# QuadCopter_Controller.net
KiCad netlist of a schematic drawn in EAGLE
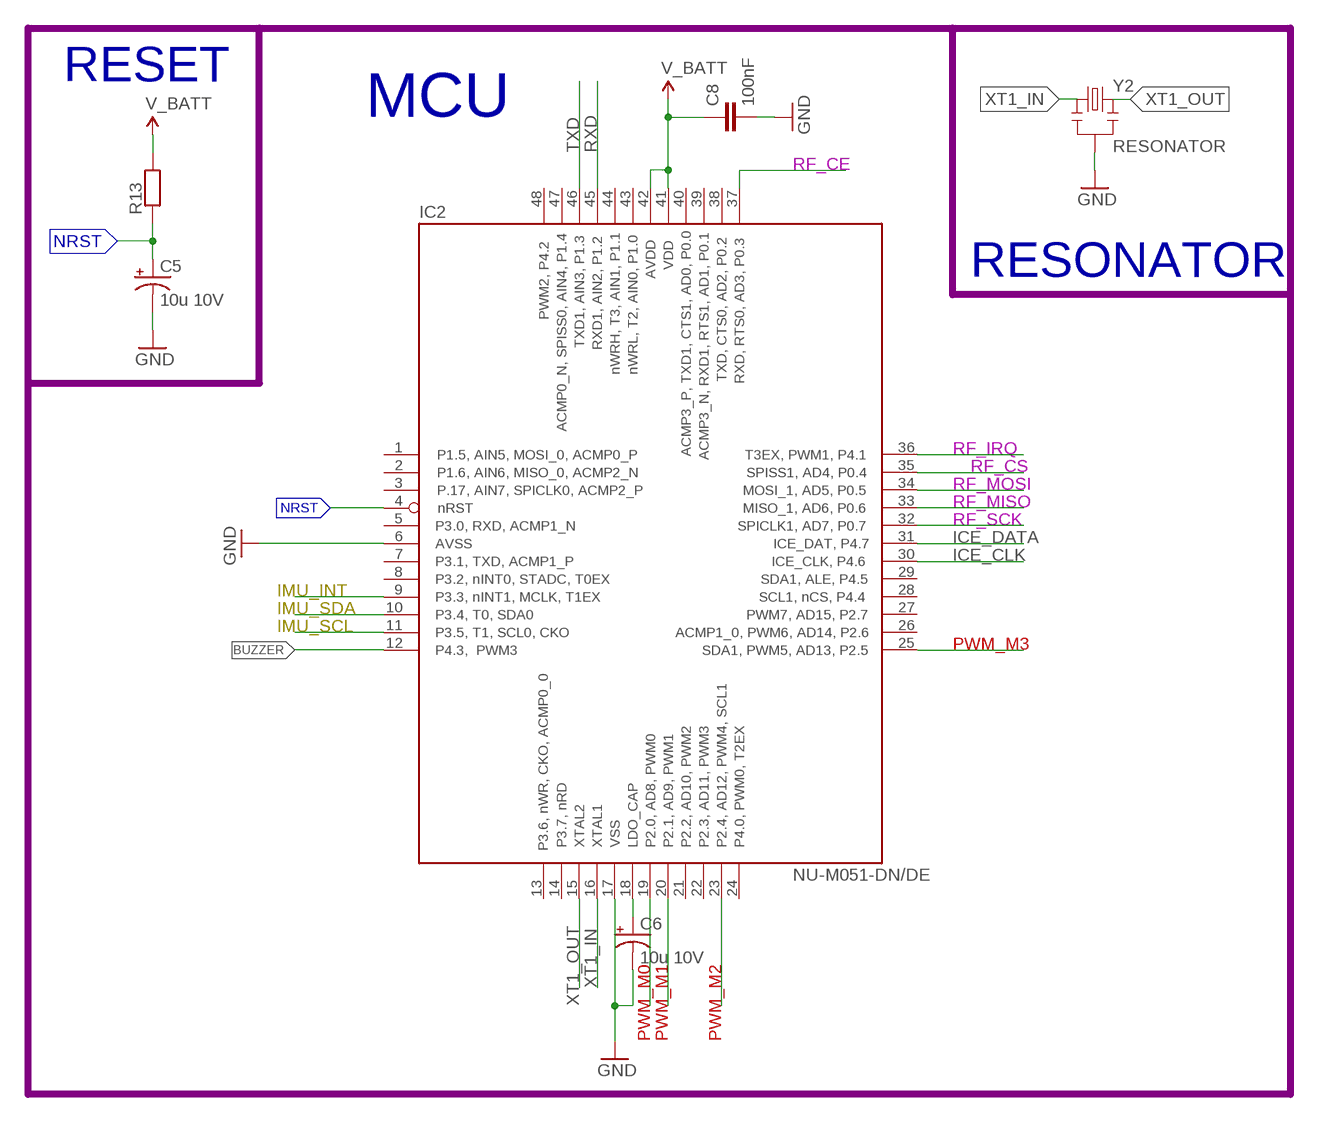
[diagram p0: schematic, sheet 1, part 1 of 2]
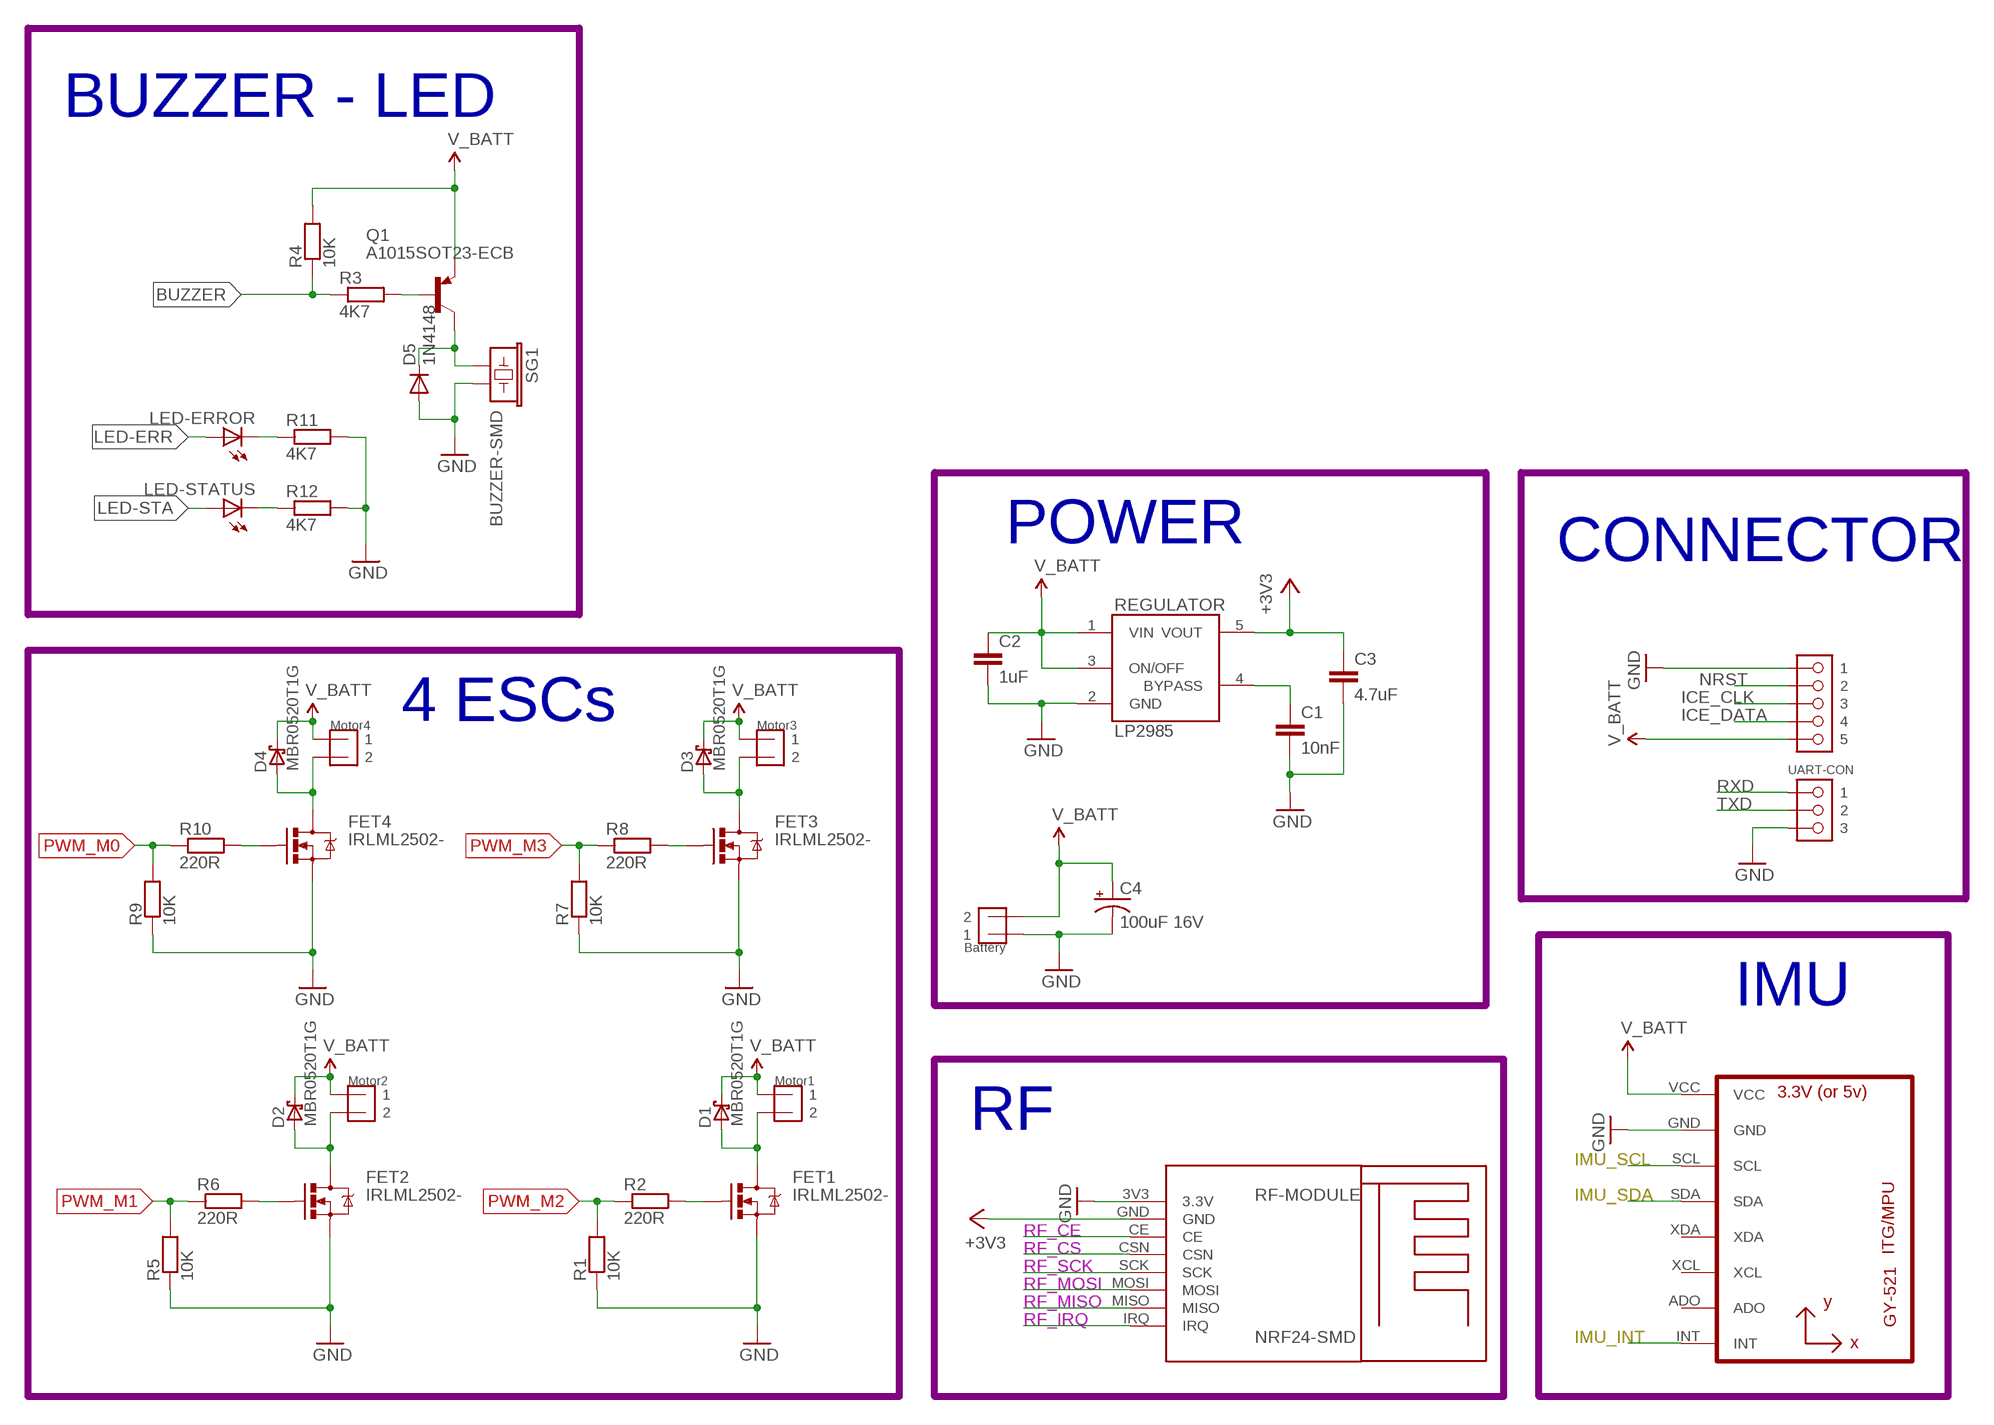
[diagram p1: schematic, sheet 1, part 2 of 2]

(export (version "E")
  (design (tool "Eeschema 10.0.6"))
  (components
    (comp (ref "BATTERY")
      (value "Battery")
      (footprint "eagle-import:WAFER-CON-2P")
      (libsource (lib "eagle-import") (part "WAFER-CON-2P"))
    )
    (comp (ref "C1")
      (value "10nF")
      (footprint "eagle-import:C0603K")
      (libsource (lib "eagle-import") (part "C-SMDC0603K"))
    )
    (comp (ref "C2")
      (value "1uF")
      (footprint "eagle-import:C0603K")
      (libsource (lib "eagle-import") (part "C-SMDC0603K"))
    )
    (comp (ref "C3")
      (value "4.7uF")
      (footprint "eagle-import:C0603K")
      (libsource (lib "eagle-import") (part "C-SMDC0603K"))
    )
    (comp (ref "C4")
      (value "100uF 16V")
      (footprint "eagle-import:PANASONIC_D")
      (libsource (lib "eagle-import") (part "C-ALU-D"))
    )
    (comp (ref "C5")
      (value "10u 10V")
      (footprint "eagle-import:EIA3216")
      (libsource (lib "eagle-import") (part "CAP_POL1206"))
    )
    (comp (ref "C6")
      (value "10u 10V")
      (footprint "eagle-import:EIA3216")
      (libsource (lib "eagle-import") (part "CAP_POL1206"))
    )
    (comp (ref "C8")
      (value "100nF")
      (footprint "eagle-import:C0603K")
      (libsource (lib "eagle-import") (part "C-SMDC0603K"))
    )
    (comp (ref "D1")
      (value "MBR0520T1G")
      (footprint "eagle-import:SOD123")
      (libsource (lib "eagle-import") (part "D-SCKYMBR0520T1G"))
    )
    (comp (ref "D2")
      (value "MBR0520T1G")
      (footprint "eagle-import:SOD123")
      (libsource (lib "eagle-import") (part "D-SCKYMBR0520T1G"))
    )
    (comp (ref "D3")
      (value "MBR0520T1G")
      (footprint "eagle-import:SOD123")
      (libsource (lib "eagle-import") (part "D-SCKYMBR0520T1G"))
    )
    (comp (ref "D4")
      (value "MBR0520T1G")
      (footprint "eagle-import:SOD123")
      (libsource (lib "eagle-import") (part "D-SCKYMBR0520T1G"))
    )
    (comp (ref "D5")
      (value "1N4148")
      (footprint "eagle-import:SOD123")
      (libsource (lib "eagle-import") (part "1N4148-SOD123"))
    )
    (comp (ref "FET1")
      (value "IRLML2502-")
      (footprint "eagle-import:SOT-23")
      (libsource (lib "eagle-import") (part "IRLML2502-"))
    )
    (comp (ref "FET2")
      (value "IRLML2502-")
      (footprint "eagle-import:SOT-23")
      (libsource (lib "eagle-import") (part "IRLML2502-"))
    )
    (comp (ref "FET3")
      (value "IRLML2502-")
      (footprint "eagle-import:SOT-23")
      (libsource (lib "eagle-import") (part "IRLML2502-"))
    )
    (comp (ref "FET4")
      (value "IRLML2502-")
      (footprint "eagle-import:SOT-23")
      (libsource (lib "eagle-import") (part "IRLML2502-"))
    )
    (comp (ref "IC2")
      (value "NU-M051-DN/DE")
      (footprint "eagle-import:LQFP48")
      (libsource (lib "eagle-import") (part "NU-M051-DN/DE"))
    )
    (comp (ref "LED-ERROR")
      (value "LED0805")
      (footprint "eagle-import:LED_0805")
      (libsource (lib "eagle-import") (part "LED0805"))
    )
    (comp (ref "LED-STATUS")
      (value "LED0805")
      (footprint "eagle-import:LED_0805")
      (libsource (lib "eagle-import") (part "LED0805"))
    )
    (comp (ref "MOTOR1")
      (value "Motor1")
      (footprint "eagle-import:WAFER-CON-2P")
      (libsource (lib "eagle-import") (part "WAFER-CON-2P"))
    )
    (comp (ref "MOTOR2")
      (value "Motor2")
      (footprint "eagle-import:WAFER-CON-2P")
      (libsource (lib "eagle-import") (part "WAFER-CON-2P"))
    )
    (comp (ref "MOTOR3")
      (value "Motor3")
      (footprint "eagle-import:WAFER-CON-2P")
      (libsource (lib "eagle-import") (part "WAFER-CON-2P"))
    )
    (comp (ref "MOTOR4")
      (value "Motor4")
      (footprint "eagle-import:WAFER-CON-2P")
      (libsource (lib "eagle-import") (part "WAFER-CON-2P"))
    )
    (comp (ref "Q1")
      (value "A1015SOT23-ECB")
      (footprint "eagle-import:SOT23-ECB")
      (libsource (lib "eagle-import") (part "A1015SOT23-ECB"))
    )
    (comp (ref "R1")
      (value "10K")
      (footprint "eagle-import:R0603")
      (libsource (lib "eagle-import") (part "RESISTOR-SMDR0603"))
    )
    (comp (ref "R2")
      (value "220R")
      (footprint "eagle-import:R0603")
      (libsource (lib "eagle-import") (part "RESISTOR-SMDR0603"))
    )
    (comp (ref "R3")
      (value "4K7")
      (footprint "eagle-import:R0805")
      (libsource (lib "eagle-import") (part "RESISTOR-SMDR0805"))
    )
    (comp (ref "R4")
      (value "10K")
      (footprint "eagle-import:R0805")
      (libsource (lib "eagle-import") (part "RESISTOR-SMDR0805"))
    )
    (comp (ref "R5")
      (value "10K")
      (footprint "eagle-import:R0603")
      (libsource (lib "eagle-import") (part "RESISTOR-SMDR0603"))
    )
    (comp (ref "R6")
      (value "220R")
      (footprint "eagle-import:R0603")
      (libsource (lib "eagle-import") (part "RESISTOR-SMDR0603"))
    )
    (comp (ref "R7")
      (value "10K")
      (footprint "eagle-import:R0603")
      (libsource (lib "eagle-import") (part "RESISTOR-SMDR0603"))
    )
    (comp (ref "R8")
      (value "220R")
      (footprint "eagle-import:R0603")
      (libsource (lib "eagle-import") (part "RESISTOR-SMDR0603"))
    )
    (comp (ref "R9")
      (value "10K")
      (footprint "eagle-import:R0603")
      (libsource (lib "eagle-import") (part "RESISTOR-SMDR0603"))
    )
    (comp (ref "R10")
      (value "220R")
      (footprint "eagle-import:R0603")
      (libsource (lib "eagle-import") (part "RESISTOR-SMDR0603"))
    )
    (comp (ref "R11")
      (value "4K7")
      (footprint "eagle-import:R0805")
      (libsource (lib "eagle-import") (part "RESISTOR-SMDR0805"))
    )
    (comp (ref "R12")
      (value "4K7")
      (footprint "eagle-import:R0805")
      (libsource (lib "eagle-import") (part "RESISTOR-SMDR0805"))
    )
    (comp (ref "R13")
      (value "RESISTOR-SMDR0603")
      (footprint "eagle-import:R0603")
      (libsource (lib "eagle-import") (part "RESISTOR-SMDR0603"))
    )
    (comp (ref "REGULATOR")
      (value "Regulator")
      (footprint "eagle-import:SOT25")
      (libsource (lib "eagle-import") (part "LP2985AIM5-3.3"))
    )
    (comp (ref "RF-MODULE")
      (value "NRF24-SMD")
      (footprint "eagle-import:NRF24-SMD")
      (libsource (lib "eagle-import") (part "NRF24-SMD"))
    )
    (comp (ref "SG1")
      (value "BUZZER-SMD")
      (footprint "eagle-import:BUZZER-CCV-KIT")
      (libsource (lib "eagle-import") (part "BUZZERSMD2-KIT"))
    )
    (comp (ref "U$1")
      (value "ICE_CON")
      (footprint "eagle-import:WAFER-CON-5P")
      (libsource (lib "eagle-import") (part "WAFER-CON-5P"))
    )
    (comp (ref "U$2")
      (value "UART-CON")
      (footprint "eagle-import:WAFER-CON-3P")
      (libsource (lib "eagle-import") (part "WAFER-CON-3P"))
    )
    (comp (ref "U1")
      (value "GY-521MPU6050")
      (footprint "eagle-import:GY-521")
      (libsource (lib "eagle-import") (part "GY-521MPU6050"))
    )
    (comp (ref "Y2")
      (value "RESONATOR")
      (footprint "eagle-import:RESONATOR-SMD")
      (libsource (lib "eagle-import") (part "RESONATOR-ARDUINO-PRO-MINISMD"))
    )
  )
  (nets
    (net (code "1") (name "+3V3") (class "Default")
      (node (ref "C3") (pin "1") (pinfunction "1_1") (pintype "passive"))
      (node (ref "REGULATOR") (pin "5") (pinfunction "VOUT_5") (pintype "power_in"))
      (node (ref "RF-MODULE") (pin "GND") (pinfunction "GND_GND") (pintype "bidirectional"))
    )
    (net (code "2") (name "/ICE_CLK") (class "Default")
      (node (ref "IC2") (pin "30") (pinfunction "30_30") (pintype "bidirectional"))
      (node (ref "U$1") (pin "P$3") (pinfunction "3_P$3") (pintype "passive"))
    )
    (net (code "3") (name "/ICE_DATA") (class "Default")
      (node (ref "IC2") (pin "31") (pinfunction "31_31") (pintype "bidirectional"))
      (node (ref "U$1") (pin "P$4") (pinfunction "4_P$4") (pintype "passive"))
    )
    (net (code "4") (name "/IMU_INT") (class "Default")
      (node (ref "IC2") (pin "9") (pinfunction "9_9") (pintype "bidirectional"))
      (node (ref "U1") (pin "INT") (pinfunction "INT_INT") (pintype "bidirectional"))
    )
    (net (code "5") (name "/IMU_SCL") (class "Default")
      (node (ref "IC2") (pin "11") (pinfunction "11_11") (pintype "bidirectional"))
      (node (ref "U1") (pin "SCL") (pinfunction "SCL_SCL") (pintype "bidirectional"))
    )
    (net (code "6") (name "/IMU_SDA") (class "Default")
      (node (ref "IC2") (pin "10") (pinfunction "10_10") (pintype "bidirectional"))
      (node (ref "U1") (pin "SDA") (pinfunction "SDA_SDA") (pintype "bidirectional"))
    )
    (net (code "7") (name "/RF_CE") (class "Default")
      (node (ref "IC2") (pin "37") (pinfunction "37_37") (pintype "bidirectional"))
      (node (ref "RF-MODULE") (pin "CE") (pinfunction "CE_CE") (pintype "bidirectional"))
    )
    (net (code "8") (name "/RF_CS") (class "Default")
      (node (ref "IC2") (pin "35") (pinfunction "35_35") (pintype "bidirectional"))
      (node (ref "RF-MODULE") (pin "CSN") (pinfunction "CSN_CSN") (pintype "bidirectional"))
    )
    (net (code "9") (name "/RF_IRQ") (class "Default")
      (node (ref "IC2") (pin "36") (pinfunction "36_36") (pintype "bidirectional"))
      (node (ref "RF-MODULE") (pin "IRQ") (pinfunction "IRQ_IRQ") (pintype "bidirectional"))
    )
    (net (code "10") (name "/RF_MISO") (class "Default")
      (node (ref "IC2") (pin "33") (pinfunction "33_33") (pintype "bidirectional"))
      (node (ref "RF-MODULE") (pin "MISO") (pinfunction "MISO_MISO") (pintype "bidirectional"))
    )
    (net (code "11") (name "/RF_MOSI") (class "Default")
      (node (ref "IC2") (pin "34") (pinfunction "34_34") (pintype "bidirectional"))
      (node (ref "RF-MODULE") (pin "MOSI") (pinfunction "MOSI_MOSI") (pintype "bidirectional"))
    )
    (net (code "12") (name "/RF_SCK") (class "Default")
      (node (ref "IC2") (pin "32") (pinfunction "32_32") (pintype "bidirectional"))
      (node (ref "RF-MODULE") (pin "SCK") (pinfunction "SCK_SCK") (pintype "bidirectional"))
    )
    (net (code "13") (name "/RXD") (class "Default")
      (node (ref "IC2") (pin "45") (pinfunction "45_45") (pintype "bidirectional"))
      (node (ref "U$2") (pin "P$1") (pinfunction "1_P$1") (pintype "passive"))
    )
    (net (code "14") (name "/TXD") (class "Default")
      (node (ref "IC2") (pin "46") (pinfunction "46_46") (pintype "bidirectional"))
      (node (ref "U$2") (pin "P$2") (pinfunction "2_P$2") (pintype "passive"))
    )
    (net (code "15") (name "BUZZER") (class "Default")
      (node (ref "IC2") (pin "12") (pinfunction "12_12") (pintype "bidirectional"))
      (node (ref "R3") (pin "1") (pinfunction "1_1") (pintype "passive"))
      (node (ref "R4") (pin "1") (pinfunction "1_1") (pintype "passive"))
    )
    (net (code "16") (name "GND") (class "Default")
      (node (ref "BATTERY") (pin "P$1") (pinfunction "1_P$1") (pintype "power_in"))
      (node (ref "C1") (pin "2") (pinfunction "2_2") (pintype "passive"))
      (node (ref "C2") (pin "2") (pinfunction "2_2") (pintype "passive"))
      (node (ref "C3") (pin "2") (pinfunction "2_2") (pintype "passive"))
      (node (ref "C4") (pin "-") (pinfunction "-_-") (pintype "passive"))
      (node (ref "C5") (pin "C") (pinfunction "-_C") (pintype "passive"))
      (node (ref "C6") (pin "C") (pinfunction "-_C") (pintype "passive"))
      (node (ref "C8") (pin "2") (pinfunction "2_2") (pintype "passive"))
      (node (ref "D5") (pin "A") (pinfunction "A_A") (pintype "passive"))
      (node (ref "FET1") (pin "2") (pinfunction "S_2") (pintype "passive"))
      (node (ref "FET2") (pin "2") (pinfunction "S_2") (pintype "passive"))
      (node (ref "FET3") (pin "2") (pinfunction "S_2") (pintype "passive"))
      (node (ref "FET4") (pin "2") (pinfunction "S_2") (pintype "passive"))
      (node (ref "IC2") (pin "17") (pinfunction "17_17") (pintype "bidirectional"))
      (node (ref "IC2") (pin "6") (pinfunction "6_6") (pintype "bidirectional"))
      (node (ref "R1") (pin "1") (pinfunction "1_1") (pintype "passive"))
      (node (ref "R11") (pin "2") (pinfunction "2_2") (pintype "passive"))
      (node (ref "R12") (pin "2") (pinfunction "2_2") (pintype "passive"))
      (node (ref "R5") (pin "1") (pinfunction "1_1") (pintype "passive"))
      (node (ref "R7") (pin "1") (pinfunction "1_1") (pintype "passive"))
      (node (ref "R9") (pin "1") (pinfunction "1_1") (pintype "passive"))
      (node (ref "REGULATOR") (pin "2") (pinfunction "GND_2") (pintype "power_in"))
      (node (ref "RF-MODULE") (pin "3V3") (pinfunction "3.3V_3V3") (pintype "bidirectional"))
      (node (ref "SG1") (pin "-") (pinfunction "2_-") (pintype "passive"))
      (node (ref "U$1") (pin "P$1") (pinfunction "1_P$1") (pintype "passive"))
      (node (ref "U$2") (pin "P$3") (pinfunction "3_P$3") (pintype "passive"))
      (node (ref "U1") (pin "GND") (pinfunction "GND_GND") (pintype "bidirectional"))
      (node (ref "Y2") (pin "2") (pinfunction "2_2") (pintype "passive"))
    )
    (net (code "17") (name "LED-ERR") (class "Default")
      (node (ref "LED-ERROR") (pin "A") (pinfunction "A_A") (pintype "passive"))
    )
    (net (code "18") (name "LED-STA") (class "Default")
      (node (ref "LED-STATUS") (pin "A") (pinfunction "A_A") (pintype "passive"))
    )
    (net (code "19") (name "NRST") (class "Default")
      (node (ref "C5") (pin "A") (pinfunction "+_A") (pintype "passive"))
      (node (ref "IC2") (pin "4") (pinfunction "4_4") (pintype "input"))
      (node (ref "R13") (pin "1") (pinfunction "1_1") (pintype "passive"))
      (node (ref "U$1") (pin "P$2") (pinfunction "2_P$2") (pintype "passive"))
    )
    (net (code "20") (name "Net-(C6-+)") (class "Default")
      (node (ref "C6") (pin "A") (pinfunction "+_A") (pintype "passive"))
      (node (ref "IC2") (pin "18") (pinfunction "18_18") (pintype "bidirectional"))
    )
    (net (code "21") (name "Net-(FET1-D)") (class "Default")
      (node (ref "D1") (pin "A") (pinfunction "A_A") (pintype "passive"))
      (node (ref "FET1") (pin "3") (pinfunction "D_3") (pintype "passive"))
      (node (ref "MOTOR1") (pin "P$2") (pinfunction "2_P$2") (pintype "power_in"))
    )
    (net (code "22") (name "Net-(FET1-G)") (class "Default")
      (node (ref "FET1") (pin "1") (pinfunction "G_1") (pintype "passive"))
      (node (ref "R2") (pin "2") (pinfunction "2_2") (pintype "passive"))
    )
    (net (code "23") (name "Net-(FET2-D)") (class "Default")
      (node (ref "D2") (pin "A") (pinfunction "A_A") (pintype "passive"))
      (node (ref "FET2") (pin "3") (pinfunction "D_3") (pintype "passive"))
      (node (ref "MOTOR2") (pin "P$2") (pinfunction "2_P$2") (pintype "power_in"))
    )
    (net (code "24") (name "Net-(FET2-G)") (class "Default")
      (node (ref "FET2") (pin "1") (pinfunction "G_1") (pintype "passive"))
      (node (ref "R6") (pin "2") (pinfunction "2_2") (pintype "passive"))
    )
    (net (code "25") (name "Net-(FET3-D)") (class "Default")
      (node (ref "D3") (pin "A") (pinfunction "A_A") (pintype "passive"))
      (node (ref "FET3") (pin "3") (pinfunction "D_3") (pintype "passive"))
      (node (ref "MOTOR3") (pin "P$2") (pinfunction "2_P$2") (pintype "power_in"))
    )
    (net (code "26") (name "Net-(FET3-G)") (class "Default")
      (node (ref "FET3") (pin "1") (pinfunction "G_1") (pintype "passive"))
      (node (ref "R8") (pin "2") (pinfunction "2_2") (pintype "passive"))
    )
    (net (code "27") (name "Net-(FET4-D)") (class "Default")
      (node (ref "D4") (pin "A") (pinfunction "A_A") (pintype "passive"))
      (node (ref "FET4") (pin "3") (pinfunction "D_3") (pintype "passive"))
      (node (ref "MOTOR4") (pin "P$2") (pinfunction "2_P$2") (pintype "power_in"))
    )
    (net (code "28") (name "Net-(FET4-G)") (class "Default")
      (node (ref "FET4") (pin "1") (pinfunction "G_1") (pintype "passive"))
      (node (ref "R10") (pin "2") (pinfunction "2_2") (pintype "passive"))
    )
    (net (code "29") (name "Net-(LED-ERROR-PadC)") (class "Default")
      (node (ref "LED-ERROR") (pin "C") (pinfunction "C_C") (pintype "passive"))
      (node (ref "R11") (pin "1") (pinfunction "1_1") (pintype "passive"))
    )
    (net (code "30") (name "Net-(LED-STATUS-PadC)") (class "Default")
      (node (ref "LED-STATUS") (pin "C") (pinfunction "C_C") (pintype "passive"))
      (node (ref "R12") (pin "1") (pinfunction "1_1") (pintype "passive"))
    )
    (net (code "31") (name "Net-(Q1-PadB)") (class "Default")
      (node (ref "Q1") (pin "B") (pinfunction "B_B") (pintype "passive"))
      (node (ref "R3") (pin "2") (pinfunction "2_2") (pintype "passive"))
    )
    (net (code "32") (name "Net-(REGULATOR-BYPASS)") (class "Default")
      (node (ref "C1") (pin "1") (pinfunction "1_1") (pintype "passive"))
      (node (ref "REGULATOR") (pin "4") (pinfunction "BYPASS_4") (pintype "power_in"))
    )
    (net (code "33") (name "Net-(SG1-1)") (class "Default")
      (node (ref "D5") (pin "C") (pinfunction "C_C") (pintype "passive"))
      (node (ref "Q1") (pin "C") (pinfunction "C_C") (pintype "passive"))
      (node (ref "SG1") (pin "+") (pinfunction "1_+") (pintype "passive"))
    )
    (net (code "34") (name "PWM_M0") (class "Default")
      (node (ref "IC2") (pin "19") (pinfunction "19_19") (pintype "bidirectional"))
      (node (ref "R10") (pin "1") (pinfunction "1_1") (pintype "passive"))
      (node (ref "R9") (pin "2") (pinfunction "2_2") (pintype "passive"))
    )
    (net (code "35") (name "PWM_M1") (class "Default")
      (node (ref "IC2") (pin "20") (pinfunction "20_20") (pintype "bidirectional"))
      (node (ref "R5") (pin "2") (pinfunction "2_2") (pintype "passive"))
      (node (ref "R6") (pin "1") (pinfunction "1_1") (pintype "passive"))
    )
    (net (code "36") (name "PWM_M2") (class "Default")
      (node (ref "IC2") (pin "23") (pinfunction "23_23") (pintype "bidirectional"))
      (node (ref "R1") (pin "2") (pinfunction "2_2") (pintype "passive"))
      (node (ref "R2") (pin "1") (pinfunction "1_1") (pintype "passive"))
    )
    (net (code "37") (name "PWM_M3") (class "Default")
      (node (ref "IC2") (pin "25") (pinfunction "25_25") (pintype "bidirectional"))
      (node (ref "R7") (pin "2") (pinfunction "2_2") (pintype "passive"))
      (node (ref "R8") (pin "1") (pinfunction "1_1") (pintype "passive"))
    )
    (net (code "38") (name "V_BATT") (class "Default")
      (node (ref "BATTERY") (pin "P$2") (pinfunction "2_P$2") (pintype "power_in"))
      (node (ref "C2") (pin "1") (pinfunction "1_1") (pintype "passive"))
      (node (ref "C4") (pin "+") (pinfunction "+_+") (pintype "passive"))
      (node (ref "C8") (pin "1") (pinfunction "1_1") (pintype "passive"))
      (node (ref "D1") (pin "C") (pinfunction "C_C") (pintype "passive"))
      (node (ref "D2") (pin "C") (pinfunction "C_C") (pintype "passive"))
      (node (ref "D3") (pin "C") (pinfunction "C_C") (pintype "passive"))
      (node (ref "D4") (pin "C") (pinfunction "C_C") (pintype "passive"))
      (node (ref "IC2") (pin "41") (pinfunction "41_41") (pintype "bidirectional"))
      (node (ref "IC2") (pin "42") (pinfunction "42_42") (pintype "bidirectional"))
      (node (ref "MOTOR1") (pin "P$1") (pinfunction "1_P$1") (pintype "power_in"))
      (node (ref "MOTOR2") (pin "P$1") (pinfunction "1_P$1") (pintype "power_in"))
      (node (ref "MOTOR3") (pin "P$1") (pinfunction "1_P$1") (pintype "power_in"))
      (node (ref "MOTOR4") (pin "P$1") (pinfunction "1_P$1") (pintype "power_in"))
      (node (ref "Q1") (pin "E") (pinfunction "E_E") (pintype "passive"))
      (node (ref "R13") (pin "2") (pinfunction "2_2") (pintype "passive"))
      (node (ref "R4") (pin "2") (pinfunction "2_2") (pintype "passive"))
      (node (ref "REGULATOR") (pin "1") (pinfunction "VIN_1") (pintype "power_in"))
      (node (ref "REGULATOR") (pin "3") (pinfunction "ON/OFF_3") (pintype "input"))
      (node (ref "U$1") (pin "P$5") (pinfunction "5_P$5") (pintype "passive"))
      (node (ref "U1") (pin "VCC") (pinfunction "VCC_VCC") (pintype "bidirectional"))
    )
    (net (code "39") (name "XT1_IN") (class "Default")
      (node (ref "IC2") (pin "16") (pinfunction "16_16") (pintype "bidirectional"))
      (node (ref "Y2") (pin "1") (pinfunction "1_1") (pintype "passive"))
    )
    (net (code "40") (name "XT1_OUT") (class "Default")
      (node (ref "IC2") (pin "15") (pinfunction "15_15") (pintype "bidirectional"))
      (node (ref "Y2") (pin "3") (pinfunction "3_3") (pintype "passive"))
    )
    (net (code "41") (name "unconnected-(IC2-Pad1)") (class "Default")
      (node (ref "IC2") (pin "1") (pinfunction "1_1") (pintype "bidirectional"))
    )
    (net (code "42") (name "unconnected-(IC2-Pad2)") (class "Default")
      (node (ref "IC2") (pin "2") (pinfunction "2_2") (pintype "bidirectional"))
    )
    (net (code "43") (name "unconnected-(IC2-Pad3)") (class "Default")
      (node (ref "IC2") (pin "3") (pinfunction "3_3") (pintype "bidirectional"))
    )
    (net (code "44") (name "unconnected-(IC2-Pad5)") (class "Default")
      (node (ref "IC2") (pin "5") (pinfunction "5_5") (pintype "bidirectional"))
    )
    (net (code "45") (name "unconnected-(IC2-Pad7)") (class "Default")
      (node (ref "IC2") (pin "7") (pinfunction "7_7") (pintype "bidirectional"))
    )
    (net (code "46") (name "unconnected-(IC2-Pad8)") (class "Default")
      (node (ref "IC2") (pin "8") (pinfunction "8_8") (pintype "bidirectional"))
    )
    (net (code "47") (name "unconnected-(IC2-Pad13)") (class "Default")
      (node (ref "IC2") (pin "13") (pinfunction "13_13") (pintype "bidirectional"))
    )
    (net (code "48") (name "unconnected-(IC2-Pad14)") (class "Default")
      (node (ref "IC2") (pin "14") (pinfunction "14_14") (pintype "bidirectional"))
    )
    (net (code "49") (name "unconnected-(IC2-Pad21)") (class "Default")
      (node (ref "IC2") (pin "21") (pinfunction "21_21") (pintype "bidirectional"))
    )
    (net (code "50") (name "unconnected-(IC2-Pad22)") (class "Default")
      (node (ref "IC2") (pin "22") (pinfunction "22_22") (pintype "bidirectional"))
    )
    (net (code "51") (name "unconnected-(IC2-Pad24)") (class "Default")
      (node (ref "IC2") (pin "24") (pinfunction "24_24") (pintype "bidirectional"))
    )
    (net (code "52") (name "unconnected-(IC2-Pad26)") (class "Default")
      (node (ref "IC2") (pin "26") (pinfunction "26_26") (pintype "bidirectional"))
    )
    (net (code "53") (name "unconnected-(IC2-Pad27)") (class "Default")
      (node (ref "IC2") (pin "27") (pinfunction "27_27") (pintype "bidirectional"))
    )
    (net (code "54") (name "unconnected-(IC2-Pad28)") (class "Default")
      (node (ref "IC2") (pin "28") (pinfunction "28_28") (pintype "bidirectional"))
    )
    (net (code "55") (name "unconnected-(IC2-Pad29)") (class "Default")
      (node (ref "IC2") (pin "29") (pinfunction "29_29") (pintype "bidirectional"))
    )
    (net (code "56") (name "unconnected-(IC2-Pad38)") (class "Default")
      (node (ref "IC2") (pin "38") (pinfunction "38_38") (pintype "bidirectional"))
    )
    (net (code "57") (name "unconnected-(IC2-Pad39)") (class "Default")
      (node (ref "IC2") (pin "39") (pinfunction "39_39") (pintype "bidirectional"))
    )
    (net (code "58") (name "unconnected-(IC2-Pad40)") (class "Default")
      (node (ref "IC2") (pin "40") (pinfunction "40_40") (pintype "bidirectional"))
    )
    (net (code "59") (name "unconnected-(IC2-Pad43)") (class "Default")
      (node (ref "IC2") (pin "43") (pinfunction "43_43") (pintype "bidirectional"))
    )
    (net (code "60") (name "unconnected-(IC2-Pad44)") (class "Default")
      (node (ref "IC2") (pin "44") (pinfunction "44_44") (pintype "bidirectional"))
    )
    (net (code "61") (name "unconnected-(IC2-Pad47)") (class "Default")
      (node (ref "IC2") (pin "47") (pinfunction "47_47") (pintype "bidirectional"))
    )
    (net (code "62") (name "unconnected-(IC2-Pad48)") (class "Default")
      (node (ref "IC2") (pin "48") (pinfunction "48_48") (pintype "bidirectional"))
    )
    (net (code "63") (name "unconnected-(U1-PadADO)") (class "Default")
      (node (ref "U1") (pin "ADO") (pinfunction "ADO_ADO") (pintype "bidirectional"))
    )
    (net (code "64") (name "unconnected-(U1-PadXCL)") (class "Default")
      (node (ref "U1") (pin "XCL") (pinfunction "XCL_XCL") (pintype "bidirectional"))
    )
    (net (code "65") (name "unconnected-(U1-PadXDA)") (class "Default")
      (node (ref "U1") (pin "XDA") (pinfunction "XDA_XDA") (pintype "bidirectional"))
    )
  )
)
